# Xblast_Jafar_-_EasyEDA_-_Schematic_Expor.net
KiCad netlist of a schematic drawn in EasyEDA
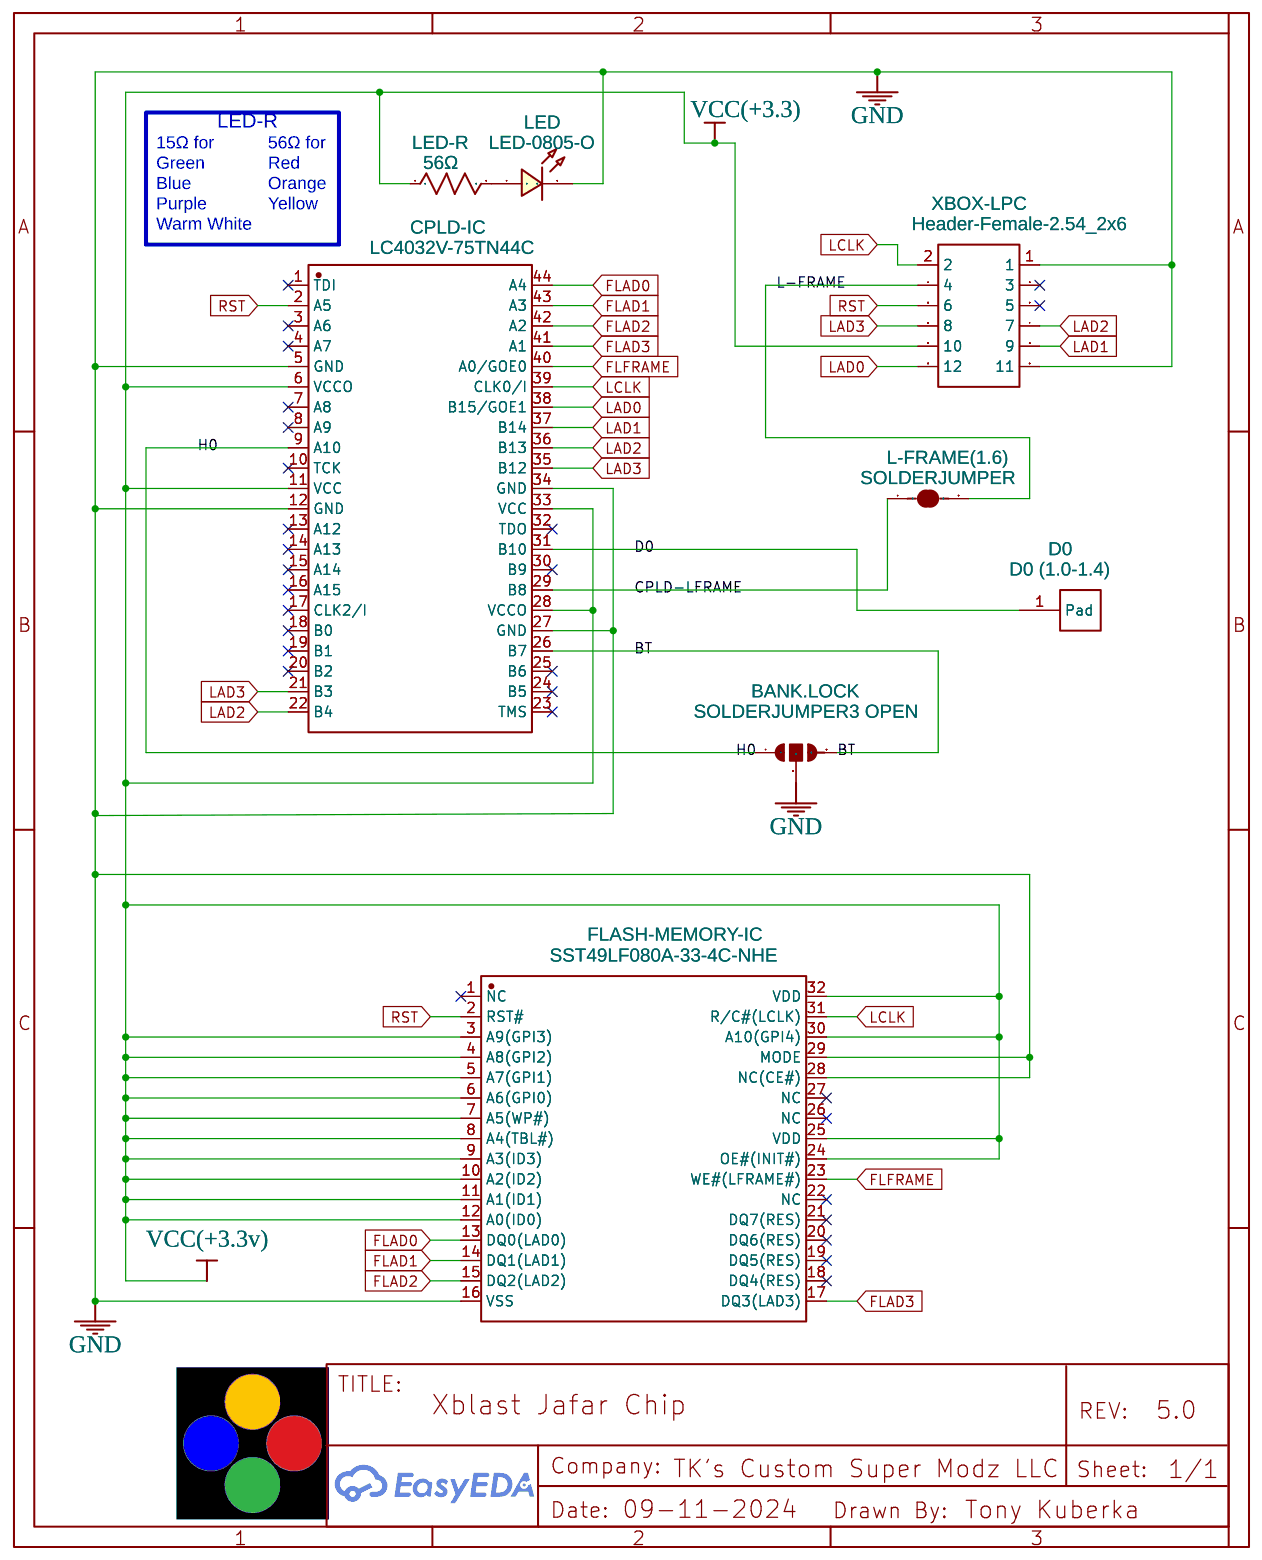
[diagram p0: schematic sheet]

(export (version "E")
  (design (tool "Eeschema 10.0.6"))
  (components
    (comp (ref "BANK.LOCK") (value "SOLDERJUMPER3 OPEN") (libsource (lib "") (part "SOLDERJUMPER3 OPEN")))
    (comp (ref "CPLD-IC")
      (value "LC4032V-75TN44C")
      (fields (field (name "Manufacturer") "LATTICE(莱迪思)"))
      (libsource (lib "") (part "LC4032V-75TN44C"))
    )
    (comp (ref "D0") (value "D0 (1.0-1.4)") (libsource (lib "") (part "SOLDER PAD")))
    (comp (ref "FLASH-MEMORY-IC")
      (value "SST49LF080A-33-4C-NHE")
      (fields (field (name "Manufacturer") "MICROCHIP(美国微芯)"))
      (libsource (lib "") (part "SST49LF080A-33-4C-NHE"))
    )
    (comp (ref "L-FRAME(1.6)") (value "SOLDERJUMPER") (libsource (lib "") (part "SOLDERJUMPER-OLDNC2")))
    (comp (ref "LED")
      (value "LED-0805-O")
      (fields
        (field (name "Manufacturer Part") "SZYY0805O")
        (field (name "Manufacturer") "Yongyu Photoelectric")
      )
      (libsource (lib "") (part "LED-0805-ORANGE"))
    )
    (comp (ref "LED-R") (value "56Ω") (libsource (lib "") (part "R_0805_US")))
    (comp (ref "XBOX-LPC")
      (value "Header-Female-2.54_2x6")
      (fields (field (name "Manufacturer Part") "2.54-2*6P母") (field (name "Manufacturer") "BOOMELE(博穆精密)"))
      (libsource (lib "") (part "Header-Female-2.54_2x6"))
    )
  )
  (nets
    (net (code "1") (name "/BT") (class "Default")
      (node (ref "BANK.LOCK") (pin "3") (pinfunction "3_3") (pintype "unspecified"))
      (node (ref "CPLD-IC") (pin "26") (pinfunction "B7_26") (pintype "unspecified"))
    )
    (net (code "2") (name "/CPLD-LFRAME") (class "Default")
      (node (ref "CPLD-IC") (pin "29") (pinfunction "B8_29") (pintype "unspecified"))
      (node (ref "L-FRAME(1.6)") (pin "1") (pinfunction "1_1") (pintype "unspecified"))
    )
    (net (code "3") (name "/D0") (class "Default")
      (node (ref "CPLD-IC") (pin "31") (pinfunction "B10_31") (pintype "unspecified"))
      (node (ref "D0") (pin "1") (pinfunction "Pad_1") (pintype "unspecified"))
    )
    (net (code "4") (name "/H0") (class "Default")
      (node (ref "BANK.LOCK") (pin "1") (pinfunction "1_1") (pintype "unspecified"))
      (node (ref "CPLD-IC") (pin "9") (pinfunction "A10_9") (pintype "unspecified"))
    )
    (net (code "5") (name "/L-FRAME") (class "Default")
      (node (ref "L-FRAME(1.6)") (pin "2") (pinfunction "2_2") (pintype "unspecified"))
      (node (ref "XBOX-LPC") (pin "4") (pinfunction "4_4") (pintype "input"))
    )
    (net (code "6") (name "FLAD0") (class "Default")
      (node (ref "CPLD-IC") (pin "44") (pinfunction "A4_44") (pintype "unspecified"))
      (node (ref "FLASH-MEMORY-IC") (pin "13") (pinfunction "DQ0(LAD0)_13") (pintype "unspecified"))
    )
    (net (code "7") (name "FLAD1") (class "Default")
      (node (ref "CPLD-IC") (pin "43") (pinfunction "A3_43") (pintype "unspecified"))
      (node (ref "FLASH-MEMORY-IC") (pin "14") (pinfunction "DQ1(LAD1)_14") (pintype "unspecified"))
    )
    (net (code "8") (name "FLAD2") (class "Default")
      (node (ref "CPLD-IC") (pin "42") (pinfunction "A2_42") (pintype "unspecified"))
      (node (ref "FLASH-MEMORY-IC") (pin "15") (pinfunction "DQ2(LAD2)_15") (pintype "unspecified"))
    )
    (net (code "9") (name "FLAD3") (class "Default")
      (node (ref "CPLD-IC") (pin "41") (pinfunction "A1_41") (pintype "unspecified"))
      (node (ref "FLASH-MEMORY-IC") (pin "17") (pinfunction "DQ3(LAD3)_17") (pintype "unspecified"))
    )
    (net (code "10") (name "FLFRAME") (class "Default")
      (node (ref "CPLD-IC") (pin "40") (pinfunction "A0/GOE0_40") (pintype "unspecified"))
      (node (ref "FLASH-MEMORY-IC") (pin "23") (pinfunction "WE#(LFRAME#)_23") (pintype "unspecified"))
    )
    (net (code "11") (name "GND") (class "Default")
      (node (ref "BANK.LOCK") (pin "2") (pinfunction "2_2") (pintype "unspecified"))
      (node (ref "CPLD-IC") (pin "12") (pinfunction "GND_12") (pintype "unspecified"))
      (node (ref "CPLD-IC") (pin "27") (pinfunction "GND_27") (pintype "unspecified"))
      (node (ref "CPLD-IC") (pin "34") (pinfunction "GND_34") (pintype "unspecified"))
      (node (ref "CPLD-IC") (pin "5") (pinfunction "GND_5") (pintype "unspecified"))
      (node (ref "FLASH-MEMORY-IC") (pin "16") (pinfunction "VSS_16") (pintype "unspecified"))
      (node (ref "FLASH-MEMORY-IC") (pin "28") (pinfunction "NC(CE#)_28") (pintype "unspecified"))
      (node (ref "FLASH-MEMORY-IC") (pin "29") (pinfunction "MODE_29") (pintype "unspecified"))
      (node (ref "LED") (pin "2") (pinfunction "2_2") (pintype "unspecified"))
      (node (ref "XBOX-LPC") (pin "1") (pinfunction "1_1") (pintype "input"))
      (node (ref "XBOX-LPC") (pin "11") (pinfunction "11_11") (pintype "input"))
    )
    (net (code "12") (name "LAD0") (class "Default")
      (node (ref "CPLD-IC") (pin "38") (pinfunction "B15/GOE1_38") (pintype "unspecified"))
      (node (ref "XBOX-LPC") (pin "12") (pinfunction "12_12") (pintype "input"))
    )
    (net (code "13") (name "LAD1") (class "Default")
      (node (ref "CPLD-IC") (pin "37") (pinfunction "B14_37") (pintype "unspecified"))
      (node (ref "XBOX-LPC") (pin "9") (pinfunction "9_9") (pintype "input"))
    )
    (net (code "14") (name "LAD2") (class "Default")
      (node (ref "CPLD-IC") (pin "22") (pinfunction "B4_22") (pintype "unspecified"))
      (node (ref "CPLD-IC") (pin "36") (pinfunction "B13_36") (pintype "unspecified"))
      (node (ref "XBOX-LPC") (pin "7") (pinfunction "7_7") (pintype "input"))
    )
    (net (code "15") (name "LAD3") (class "Default")
      (node (ref "CPLD-IC") (pin "21") (pinfunction "B3_21") (pintype "unspecified"))
      (node (ref "CPLD-IC") (pin "35") (pinfunction "B12_35") (pintype "unspecified"))
      (node (ref "XBOX-LPC") (pin "8") (pinfunction "8_8") (pintype "input"))
    )
    (net (code "16") (name "LCLK") (class "Default")
      (node (ref "CPLD-IC") (pin "39") (pinfunction "CLK0/I_39") (pintype "unspecified"))
      (node (ref "FLASH-MEMORY-IC") (pin "31") (pinfunction "R/C#(LCLK)_31") (pintype "unspecified"))
      (node (ref "XBOX-LPC") (pin "2") (pinfunction "2_2") (pintype "input"))
    )
    (net (code "17") (name "Net-(LED-Pad1)") (class "Default")
      (node (ref "LED") (pin "1") (pinfunction "1_1") (pintype "unspecified"))
      (node (ref "LED-R") (pin "2") (pinfunction "2_2") (pintype "unspecified"))
    )
    (net (code "18") (name "RST") (class "Default")
      (node (ref "CPLD-IC") (pin "2") (pinfunction "A5_2") (pintype "unspecified"))
      (node (ref "FLASH-MEMORY-IC") (pin "2") (pinfunction "RST#_2") (pintype "unspecified"))
      (node (ref "XBOX-LPC") (pin "6") (pinfunction "6_6") (pintype "input"))
    )
    (net (code "19") (name "VCC(+3.3)") (class "Default")
      (node (ref "CPLD-IC") (pin "11") (pinfunction "VCC_11") (pintype "unspecified"))
      (node (ref "CPLD-IC") (pin "28") (pinfunction "VCCO_28") (pintype "unspecified"))
      (node (ref "CPLD-IC") (pin "33") (pinfunction "VCC_33") (pintype "unspecified"))
      (node (ref "CPLD-IC") (pin "6") (pinfunction "VCCO_6") (pintype "unspecified"))
      (node (ref "FLASH-MEMORY-IC") (pin "10") (pinfunction "A2(ID2)_10") (pintype "unspecified"))
      (node (ref "FLASH-MEMORY-IC") (pin "11") (pinfunction "A1(ID1)_11") (pintype "unspecified"))
      (node (ref "FLASH-MEMORY-IC") (pin "12") (pinfunction "A0(ID0)_12") (pintype "unspecified"))
      (node (ref "FLASH-MEMORY-IC") (pin "24") (pinfunction "OE#(INIT#)_24") (pintype "unspecified"))
      (node (ref "FLASH-MEMORY-IC") (pin "25") (pinfunction "VDD_25") (pintype "unspecified"))
      (node (ref "FLASH-MEMORY-IC") (pin "3") (pinfunction "A9(GPI3)_3") (pintype "unspecified"))
      (node (ref "FLASH-MEMORY-IC") (pin "30") (pinfunction "A10(GPI4)_30") (pintype "unspecified"))
      (node (ref "FLASH-MEMORY-IC") (pin "32") (pinfunction "VDD_32") (pintype "unspecified"))
      (node (ref "FLASH-MEMORY-IC") (pin "4") (pinfunction "A8(GPI2)_4") (pintype "unspecified"))
      (node (ref "FLASH-MEMORY-IC") (pin "5") (pinfunction "A7(GPI1)_5") (pintype "unspecified"))
      (node (ref "FLASH-MEMORY-IC") (pin "6") (pinfunction "A6(GPI0)_6") (pintype "unspecified"))
      (node (ref "FLASH-MEMORY-IC") (pin "7") (pinfunction "A5(WP#)_7") (pintype "unspecified"))
      (node (ref "FLASH-MEMORY-IC") (pin "8") (pinfunction "A4(TBL#)_8") (pintype "unspecified"))
      (node (ref "FLASH-MEMORY-IC") (pin "9") (pinfunction "A3(ID3)_9") (pintype "unspecified"))
      (node (ref "LED-R") (pin "1") (pinfunction "1_1") (pintype "unspecified"))
      (node (ref "XBOX-LPC") (pin "10") (pinfunction "10_10") (pintype "input"))
    )
    (net (code "20") (name "unconnected-(CPLD-IC-A6-Pad3)") (class "Default")
      (node (ref "CPLD-IC") (pin "3") (pinfunction "A6_3") (pintype "unspecified+no_connect"))
    )
    (net (code "21") (name "unconnected-(CPLD-IC-A7-Pad4)") (class "Default")
      (node (ref "CPLD-IC") (pin "4") (pinfunction "A7_4") (pintype "unspecified+no_connect"))
    )
    (net (code "22") (name "unconnected-(CPLD-IC-A8-Pad7)") (class "Default")
      (node (ref "CPLD-IC") (pin "7") (pinfunction "A8_7") (pintype "unspecified+no_connect"))
    )
    (net (code "23") (name "unconnected-(CPLD-IC-A9-Pad8)") (class "Default")
      (node (ref "CPLD-IC") (pin "8") (pinfunction "A9_8") (pintype "unspecified+no_connect"))
    )
    (net (code "24") (name "unconnected-(CPLD-IC-A12-Pad13)") (class "Default")
      (node (ref "CPLD-IC") (pin "13") (pinfunction "A12_13") (pintype "unspecified+no_connect"))
    )
    (net (code "25") (name "unconnected-(CPLD-IC-A13-Pad14)") (class "Default")
      (node (ref "CPLD-IC") (pin "14") (pinfunction "A13_14") (pintype "unspecified+no_connect"))
    )
    (net (code "26") (name "unconnected-(CPLD-IC-A14-Pad15)") (class "Default")
      (node (ref "CPLD-IC") (pin "15") (pinfunction "A14_15") (pintype "unspecified+no_connect"))
    )
    (net (code "27") (name "unconnected-(CPLD-IC-A15-Pad16)") (class "Default")
      (node (ref "CPLD-IC") (pin "16") (pinfunction "A15_16") (pintype "unspecified+no_connect"))
    )
    (net (code "28") (name "unconnected-(CPLD-IC-B0-Pad18)") (class "Default")
      (node (ref "CPLD-IC") (pin "18") (pinfunction "B0_18") (pintype "unspecified+no_connect"))
    )
    (net (code "29") (name "unconnected-(CPLD-IC-B1-Pad19)") (class "Default")
      (node (ref "CPLD-IC") (pin "19") (pinfunction "B1_19") (pintype "unspecified+no_connect"))
    )
    (net (code "30") (name "unconnected-(CPLD-IC-B2-Pad20)") (class "Default")
      (node (ref "CPLD-IC") (pin "20") (pinfunction "B2_20") (pintype "unspecified+no_connect"))
    )
    (net (code "31") (name "unconnected-(CPLD-IC-B5-Pad24)") (class "Default")
      (node (ref "CPLD-IC") (pin "24") (pinfunction "B5_24") (pintype "unspecified+no_connect"))
    )
    (net (code "32") (name "unconnected-(CPLD-IC-B6-Pad25)") (class "Default")
      (node (ref "CPLD-IC") (pin "25") (pinfunction "B6_25") (pintype "unspecified+no_connect"))
    )
    (net (code "33") (name "unconnected-(CPLD-IC-B9-Pad30)") (class "Default")
      (node (ref "CPLD-IC") (pin "30") (pinfunction "B9_30") (pintype "unspecified+no_connect"))
    )
    (net (code "34") (name "unconnected-(CPLD-IC-CLK2{slash}I-Pad17)") (class "Default")
      (node (ref "CPLD-IC") (pin "17") (pinfunction "CLK2/I_17") (pintype "unspecified+no_connect"))
    )
    (net (code "35") (name "unconnected-(CPLD-IC-TCK-Pad10)") (class "Default")
      (node (ref "CPLD-IC") (pin "10") (pinfunction "TCK_10") (pintype "unspecified+no_connect"))
    )
    (net (code "36") (name "unconnected-(CPLD-IC-TDI-Pad1)") (class "Default")
      (node (ref "CPLD-IC") (pin "1") (pinfunction "TDI_1") (pintype "unspecified+no_connect"))
    )
    (net (code "37") (name "unconnected-(CPLD-IC-TDO-Pad32)") (class "Default")
      (node (ref "CPLD-IC") (pin "32") (pinfunction "TDO_32") (pintype "unspecified+no_connect"))
    )
    (net (code "38") (name "unconnected-(CPLD-IC-TMS-Pad23)") (class "Default")
      (node (ref "CPLD-IC") (pin "23") (pinfunction "TMS_23") (pintype "unspecified+no_connect"))
    )
    (net (code "39") (name "unconnected-(FLASH-MEMORY-IC-DQ4(RES)-Pad18)") (class "Default")
      (node (ref "FLASH-MEMORY-IC") (pin "18") (pinfunction "DQ4(RES)_18") (pintype "unspecified+no_connect"))
    )
    (net (code "40") (name "unconnected-(FLASH-MEMORY-IC-DQ5(RES)-Pad19)") (class "Default")
      (node (ref "FLASH-MEMORY-IC") (pin "19") (pinfunction "DQ5(RES)_19") (pintype "unspecified+no_connect"))
    )
    (net (code "41") (name "unconnected-(FLASH-MEMORY-IC-DQ6(RES)-Pad20)") (class "Default")
      (node (ref "FLASH-MEMORY-IC") (pin "20") (pinfunction "DQ6(RES)_20") (pintype "unspecified+no_connect"))
    )
    (net (code "42") (name "unconnected-(FLASH-MEMORY-IC-DQ7(RES)-Pad21)") (class "Default")
      (node (ref "FLASH-MEMORY-IC") (pin "21") (pinfunction "DQ7(RES)_21") (pintype "unspecified+no_connect"))
    )
    (net (code "43") (name "unconnected-(FLASH-MEMORY-IC-NC-Pad1)") (class "Default")
      (node (ref "FLASH-MEMORY-IC") (pin "1") (pinfunction "NC_1") (pintype "unspecified+no_connect"))
    )
    (net (code "44") (name "unconnected-(FLASH-MEMORY-IC-NC-Pad22)") (class "Default")
      (node (ref "FLASH-MEMORY-IC") (pin "22") (pinfunction "NC_22") (pintype "unspecified+no_connect"))
    )
    (net (code "45") (name "unconnected-(FLASH-MEMORY-IC-NC-Pad26)") (class "Default")
      (node (ref "FLASH-MEMORY-IC") (pin "26") (pinfunction "NC_26") (pintype "unspecified+no_connect"))
    )
    (net (code "46") (name "unconnected-(FLASH-MEMORY-IC-NC-Pad27)") (class "Default")
      (node (ref "FLASH-MEMORY-IC") (pin "27") (pinfunction "NC_27") (pintype "unspecified+no_connect"))
    )
    (net (code "47") (name "unconnected-(XBOX-LPC-Pad3)") (class "Default")
      (node (ref "XBOX-LPC") (pin "3") (pinfunction "3_3") (pintype "input+no_connect"))
    )
    (net (code "48") (name "unconnected-(XBOX-LPC-Pad5)") (class "Default")
      (node (ref "XBOX-LPC") (pin "5") (pinfunction "5_5") (pintype "input+no_connect"))
    )
  )
)
